# SquidPage.net
KiCad netlist of a schematic drawn in Altium Designer
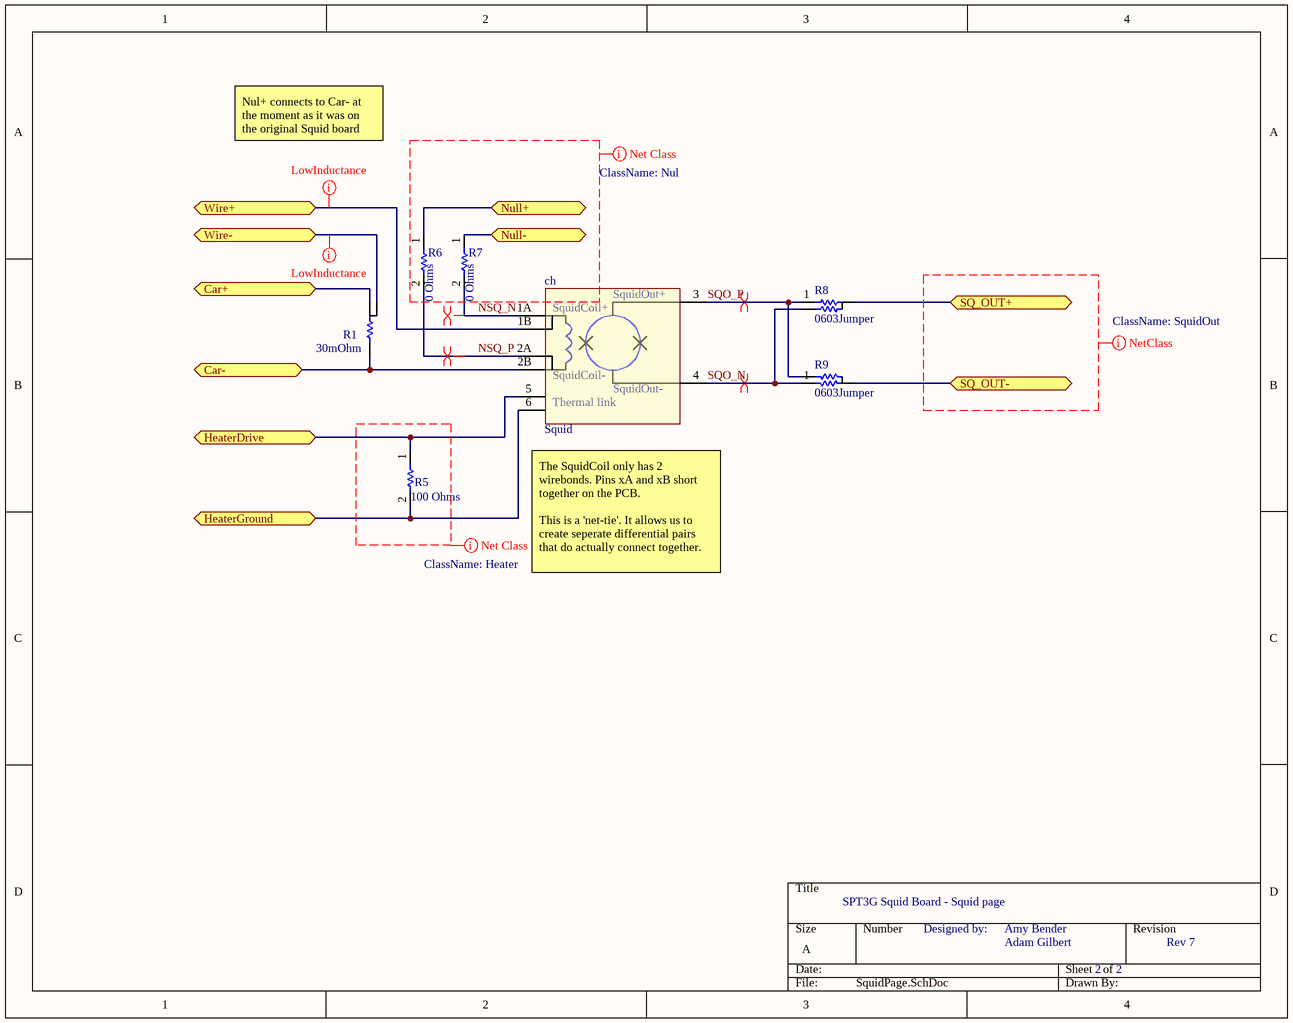
[diagram p0: SquidPage.SchDoc]

(export (version "E")
  (design (tool "Eeschema 10.0.6"))
  (components
    (comp (ref "ch") (value "Squid") (footprint "Squid2") (libsource (lib "SPT3G_LCBoard") (part "Squid")))
    (comp (ref "R1")
      (value "30mOhm")
      (footprint "0805NetTie")
      (description "Resistor")
      (fields (field (name "Comment") "ResBias"))
      (libsource (lib "SPT3G_LCBoard") (part "ResBias"))
    )
    (comp (ref "R5")
      (value "100 Ohms")
      (footprint "0603-NoSilk")
      (description "Resistor")
      (fields (field (name "Comment") "ResSquidBoard"))
      (libsource (lib "SPT3G_LCBoard") (part "ResSquidBoard"))
    )
    (comp (ref "R6")
      (value "0 Ohms")
      (footprint "0603")
      (description "Resistor")
      (fields (field (name "Comment") "ResSquidBoard"))
      (libsource (lib "SPT3G_LCBoard") (part "ResSquidBoard"))
    )
    (comp (ref "R7")
      (value "0 Ohms")
      (footprint "0603")
      (description "Resistor")
      (fields (field (name "Comment") "ResSquidBoard"))
      (libsource (lib "SPT3G_LCBoard") (part "ResSquidBoard"))
    )
    (comp (ref "R8")
      (value "0603Jumper")
      (footprint "0603-jumper")
      (description "RES 1 OHM 1/10W 1% 0603 SMD")
      (libsource (lib "SPT3G_LCBoard") (part "0603Jumper"))
    )
    (comp (ref "R9")
      (value "0603Jumper")
      (footprint "0603-jumper")
      (description "RES 1 OHM 1/10W 1% 0603 SMD")
      (libsource (lib "SPT3G_LCBoard") (part "0603Jumper"))
    )
  )
  (nets
    (net (code "1") (name "/Car+") (class "Default")
      (node (ref "R1") (pin "2A") (pinfunction "2_2A") (pintype "passive"))
    )
    (net (code "2") (name "/Car-") (class "Default")
      (node (ref "R1") (pin "1") (pinfunction "1_1") (pintype "passive"))
      (node (ref "ch") (pin "2B") (pinfunction "SquidCoil-_2B") (pintype "passive"))
    )
    (net (code "3") (name "/HeaterDrive") (class "Default")
      (node (ref "R5") (pin "1") (pinfunction "1_1") (pintype "passive"))
      (node (ref "ch") (pin "5") (pinfunction "Heater_5") (pintype "passive"))
    )
    (net (code "4") (name "/HeaterGround") (class "Default")
      (node (ref "R5") (pin "2") (pinfunction "2_2") (pintype "passive"))
      (node (ref "ch") (pin "6") (pinfunction "HeaterGnd_6") (pintype "passive"))
    )
    (net (code "5") (name "/NSQ_N") (class "Default")
      (node (ref "R7") (pin "2") (pinfunction "2_2") (pintype "passive"))
      (node (ref "ch") (pin "1A") (pinfunction "SquidCoil+_1A") (pintype "passive"))
    )
    (net (code "6") (name "/NSQ_P") (class "Default")
      (node (ref "R6") (pin "2") (pinfunction "2_2") (pintype "passive"))
      (node (ref "ch") (pin "2A") (pinfunction "SquidCoil-_2A") (pintype "passive"))
    )
    (net (code "7") (name "/Null+") (class "Default")
      (node (ref "R6") (pin "1") (pinfunction "1_1") (pintype "passive"))
    )
    (net (code "8") (name "/Null-") (class "Default")
      (node (ref "R7") (pin "1") (pinfunction "1_1") (pintype "passive"))
    )
    (net (code "9") (name "/SQO_N") (class "Default")
      (node (ref "R8") (pin "3") (pinfunction "3_3") (pintype "passive"))
      (node (ref "R9") (pin "1") (pinfunction "1_1") (pintype "passive"))
      (node (ref "ch") (pin "4") (pinfunction "SQUID-_4") (pintype "passive"))
    )
    (net (code "10") (name "/SQO_P") (class "Default")
      (node (ref "R8") (pin "1") (pinfunction "1_1") (pintype "passive"))
      (node (ref "R9") (pin "3") (pinfunction "3_3") (pintype "passive"))
      (node (ref "ch") (pin "3") (pinfunction "SQUID+_3") (pintype "passive"))
    )
    (net (code "11") (name "/SQ_OUT+") (class "Default")
      (node (ref "R8") (pin "2") (pinfunction "2_2") (pintype "passive"))
    )
    (net (code "12") (name "/SQ_OUT-") (class "Default")
      (node (ref "R9") (pin "2") (pinfunction "2_2") (pintype "passive"))
    )
    (net (code "13") (name "/Wire+") (class "Default")
      (node (ref "ch") (pin "1B") (pinfunction "SquidCoil+_1B") (pintype "passive"))
    )
    (net (code "14") (name "/Wire-") (class "Default")
      (node (ref "R1") (pin "2B") (pinfunction "2_2B") (pintype "passive"))
    )
  )
)
